# Control_Board.net
KiCad netlist of a schematic drawn in EAGLE
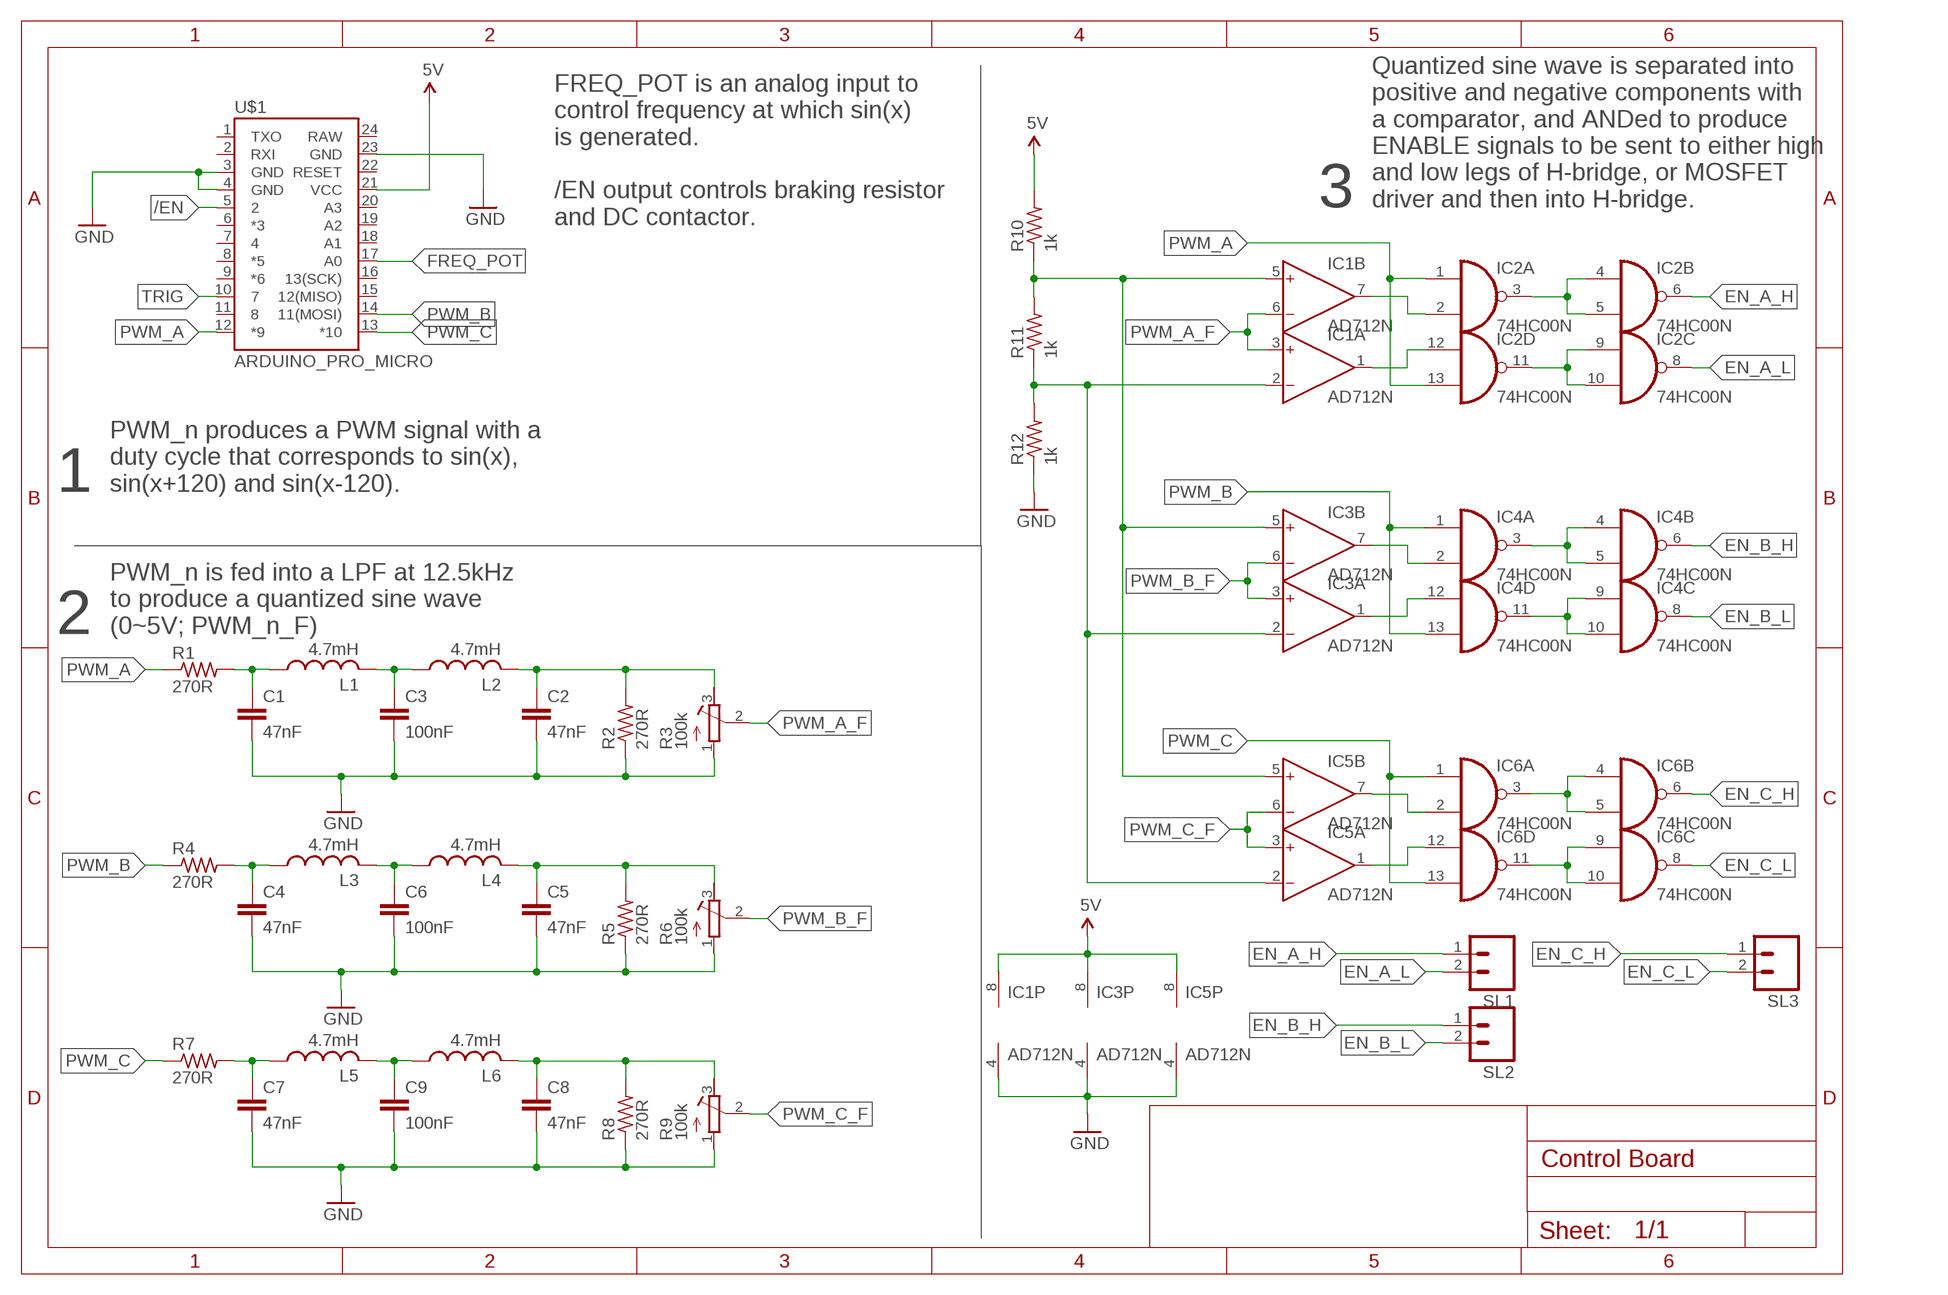
[diagram p0: schematic, sheet 1]

(export (version "E")
  (design (tool "Eeschema 10.0.6"))
  (components
    (comp (ref "C1")
      (value "47nF")
      (footprint "eagle-import:C025-025X050")
      (libsource (lib "eagle-import") (part "C-EU025-025X050"))
    )
    (comp (ref "C2")
      (value "47nF")
      (footprint "eagle-import:C025-025X050")
      (libsource (lib "eagle-import") (part "C-EU025-025X050"))
    )
    (comp (ref "C3")
      (value "100nF")
      (footprint "eagle-import:C025-025X050")
      (libsource (lib "eagle-import") (part "C-EU025-025X050"))
    )
    (comp (ref "C4")
      (value "47nF")
      (footprint "eagle-import:C025-025X050")
      (libsource (lib "eagle-import") (part "C-EU025-025X050"))
    )
    (comp (ref "C5")
      (value "47nF")
      (footprint "eagle-import:C025-025X050")
      (libsource (lib "eagle-import") (part "C-EU025-025X050"))
    )
    (comp (ref "C6")
      (value "100nF")
      (footprint "eagle-import:C025-025X050")
      (libsource (lib "eagle-import") (part "C-EU025-025X050"))
    )
    (comp (ref "C7")
      (value "47nF")
      (footprint "eagle-import:C025-025X050")
      (libsource (lib "eagle-import") (part "C-EU025-025X050"))
    )
    (comp (ref "C8")
      (value "47nF")
      (footprint "eagle-import:C025-025X050")
      (libsource (lib "eagle-import") (part "C-EU025-025X050"))
    )
    (comp (ref "C9")
      (value "100nF")
      (footprint "eagle-import:C025-025X050")
      (libsource (lib "eagle-import") (part "C-EU025-025X050"))
    )
    (comp (ref "IC1")
      (value "AD712N")
      (footprint "eagle-import:DIL08")
      (fields (field (name "MF") "ALTERA CORPORATION") (field (name "MPN") "AD712JNZ"))
      (libsource (lib "eagle-import") (part "AD712N"))
    )
    (comp (ref "IC2")
      (value "74HC00N")
      (footprint "eagle-import:DIL14")
      (libsource (lib "eagle-import") (part "7400NHC"))
    )
    (comp (ref "IC3")
      (value "AD712N")
      (footprint "eagle-import:DIL08")
      (fields (field (name "MF") "ALTERA CORPORATION") (field (name "MPN") "AD712JNZ"))
      (libsource (lib "eagle-import") (part "AD712N"))
    )
    (comp (ref "IC4")
      (value "74HC00N")
      (footprint "eagle-import:DIL14")
      (libsource (lib "eagle-import") (part "7400NHC"))
    )
    (comp (ref "IC5")
      (value "AD712N")
      (footprint "eagle-import:DIL08")
      (fields (field (name "MF") "ALTERA CORPORATION") (field (name "MPN") "AD712JNZ"))
      (libsource (lib "eagle-import") (part "AD712N"))
    )
    (comp (ref "IC6")
      (value "74HC00N")
      (footprint "eagle-import:DIL14")
      (libsource (lib "eagle-import") (part "7400NHC"))
    )
    (comp (ref "L1")
      (value "4.7mH")
      (footprint "eagle-import:0207_12")
      (libsource (lib "eagle-import") (part "L-US0207/12"))
    )
    (comp (ref "L2")
      (value "4.7mH")
      (footprint "eagle-import:0207_12")
      (libsource (lib "eagle-import") (part "L-US0207/12"))
    )
    (comp (ref "L3")
      (value "4.7mH")
      (footprint "eagle-import:0207_12")
      (libsource (lib "eagle-import") (part "L-US0207/12"))
    )
    (comp (ref "L4")
      (value "4.7mH")
      (footprint "eagle-import:0207_12")
      (libsource (lib "eagle-import") (part "L-US0207/12"))
    )
    (comp (ref "L5")
      (value "4.7mH")
      (footprint "eagle-import:0207_12")
      (libsource (lib "eagle-import") (part "L-US0207/12"))
    )
    (comp (ref "L6")
      (value "4.7mH")
      (footprint "eagle-import:0207_12")
      (libsource (lib "eagle-import") (part "L-US0207/12"))
    )
    (comp (ref "R1")
      (value "270R")
      (footprint "eagle-import:0207_7")
      (libsource (lib "eagle-import") (part "R-US_0207/7"))
    )
    (comp (ref "R2")
      (value "270R")
      (footprint "eagle-import:0207_7")
      (libsource (lib "eagle-import") (part "R-US_0207/7"))
    )
    (comp (ref "R3")
      (value "100k")
      (footprint "eagle-import:RTRIM3296W")
      (libsource (lib "eagle-import") (part "R-TRIMM3296W"))
    )
    (comp (ref "R4")
      (value "270R")
      (footprint "eagle-import:0207_7")
      (libsource (lib "eagle-import") (part "R-US_0207/7"))
    )
    (comp (ref "R5")
      (value "270R")
      (footprint "eagle-import:0207_7")
      (libsource (lib "eagle-import") (part "R-US_0207/7"))
    )
    (comp (ref "R6")
      (value "100k")
      (footprint "eagle-import:RTRIM3296W")
      (libsource (lib "eagle-import") (part "R-TRIMM3296W"))
    )
    (comp (ref "R7")
      (value "270R")
      (footprint "eagle-import:0207_7")
      (libsource (lib "eagle-import") (part "R-US_0207/7"))
    )
    (comp (ref "R8")
      (value "270R")
      (footprint "eagle-import:0207_7")
      (libsource (lib "eagle-import") (part "R-US_0207/7"))
    )
    (comp (ref "R9")
      (value "100k")
      (footprint "eagle-import:RTRIM3296W")
      (libsource (lib "eagle-import") (part "R-TRIMM3296W"))
    )
    (comp (ref "R10")
      (value "1k")
      (footprint "eagle-import:0207_7")
      (libsource (lib "eagle-import") (part "R-US_0207/7"))
    )
    (comp (ref "R11")
      (value "1k")
      (footprint "eagle-import:0207_7")
      (libsource (lib "eagle-import") (part "R-US_0207/7"))
    )
    (comp (ref "R12")
      (value "1k")
      (footprint "eagle-import:0207_7")
      (libsource (lib "eagle-import") (part "R-US_0207/7"))
    )
    (comp (ref "SL1")
      (value "M02PTH")
      (footprint "eagle-import:1X02")
      (libsource (lib "eagle-import") (part "M02PTH"))
    )
    (comp (ref "SL2")
      (value "M02PTH")
      (footprint "eagle-import:1X02")
      (libsource (lib "eagle-import") (part "M02PTH"))
    )
    (comp (ref "SL3")
      (value "M02PTH")
      (footprint "eagle-import:1X02")
      (libsource (lib "eagle-import") (part "M02PTH"))
    )
    (comp (ref "U$1")
      (value "ARDUINO_PRO_MICRO")
      (footprint "eagle-import:ARDUINO_PRO_MICRO")
      (libsource (lib "eagle-import") (part "ARDUINO_PRO_MICRO"))
    )
  )
  (nets
    (net (code "1") (name "5V") (class "Default")
      (node (ref "IC1") (pin "8") (pinfunction "V+_8") (pintype "power_in"))
      (node (ref "IC3") (pin "8") (pinfunction "V+_8") (pintype "power_in"))
      (node (ref "IC5") (pin "8") (pinfunction "V+_8") (pintype "power_in"))
      (node (ref "R10") (pin "2") (pinfunction "2_2") (pintype "passive"))
      (node (ref "U$1") (pin "21") (pinfunction "VCC_21") (pintype "bidirectional"))
    )
    (net (code "2") (name "EN_A_H") (class "Default")
      (node (ref "IC2") (pin "6") (pinfunction "O_6") (pintype "output"))
      (node (ref "SL1") (pin "1") (pinfunction "1_1") (pintype "passive"))
    )
    (net (code "3") (name "EN_A_L") (class "Default")
      (node (ref "IC2") (pin "8") (pinfunction "O_8") (pintype "output"))
      (node (ref "SL1") (pin "2") (pinfunction "2_2") (pintype "passive"))
    )
    (net (code "4") (name "EN_B_H") (class "Default")
      (node (ref "IC4") (pin "6") (pinfunction "O_6") (pintype "output"))
      (node (ref "SL2") (pin "1") (pinfunction "1_1") (pintype "passive"))
    )
    (net (code "5") (name "EN_B_L") (class "Default")
      (node (ref "IC4") (pin "8") (pinfunction "O_8") (pintype "output"))
      (node (ref "SL2") (pin "2") (pinfunction "2_2") (pintype "passive"))
    )
    (net (code "6") (name "EN_C_H") (class "Default")
      (node (ref "IC6") (pin "6") (pinfunction "O_6") (pintype "output"))
      (node (ref "SL3") (pin "1") (pinfunction "1_1") (pintype "passive"))
    )
    (net (code "7") (name "EN_C_L") (class "Default")
      (node (ref "IC6") (pin "8") (pinfunction "O_8") (pintype "output"))
      (node (ref "SL3") (pin "2") (pinfunction "2_2") (pintype "passive"))
    )
    (net (code "8") (name "FREQ_POT") (class "Default")
      (node (ref "U$1") (pin "17") (pinfunction "A0_17") (pintype "bidirectional"))
    )
    (net (code "9") (name "GND") (class "Default")
      (node (ref "C1") (pin "2") (pinfunction "2_2") (pintype "passive"))
      (node (ref "C2") (pin "2") (pinfunction "2_2") (pintype "passive"))
      (node (ref "C3") (pin "2") (pinfunction "2_2") (pintype "passive"))
      (node (ref "C4") (pin "2") (pinfunction "2_2") (pintype "passive"))
      (node (ref "C5") (pin "2") (pinfunction "2_2") (pintype "passive"))
      (node (ref "C6") (pin "2") (pinfunction "2_2") (pintype "passive"))
      (node (ref "C7") (pin "2") (pinfunction "2_2") (pintype "passive"))
      (node (ref "C8") (pin "2") (pinfunction "2_2") (pintype "passive"))
      (node (ref "C9") (pin "2") (pinfunction "2_2") (pintype "passive"))
      (node (ref "IC1") (pin "4") (pinfunction "V-_4") (pintype "power_in"))
      (node (ref "IC3") (pin "4") (pinfunction "V-_4") (pintype "power_in"))
      (node (ref "IC5") (pin "4") (pinfunction "V-_4") (pintype "power_in"))
      (node (ref "R12") (pin "1") (pinfunction "1_1") (pintype "passive"))
      (node (ref "R2") (pin "1") (pinfunction "1_1") (pintype "passive"))
      (node (ref "R3") (pin "1") (pinfunction "A_1") (pintype "passive"))
      (node (ref "R5") (pin "1") (pinfunction "1_1") (pintype "passive"))
      (node (ref "R6") (pin "1") (pinfunction "A_1") (pintype "passive"))
      (node (ref "R8") (pin "1") (pinfunction "1_1") (pintype "passive"))
      (node (ref "R9") (pin "1") (pinfunction "A_1") (pintype "passive"))
      (node (ref "U$1") (pin "23") (pinfunction "GND_23") (pintype "bidirectional"))
      (node (ref "U$1") (pin "3") (pinfunction "GND_3") (pintype "bidirectional"))
      (node (ref "U$1") (pin "4") (pinfunction "GND_4") (pintype "bidirectional"))
    )
    (net (code "10") (name "Net-(C1-Pad1)") (class "Default")
      (node (ref "C1") (pin "1") (pinfunction "1_1") (pintype "passive"))
      (node (ref "L1") (pin "1") (pinfunction "1_1") (pintype "passive"))
      (node (ref "R1") (pin "2") (pinfunction "2_2") (pintype "passive"))
    )
    (net (code "11") (name "Net-(C3-Pad1)") (class "Default")
      (node (ref "C3") (pin "1") (pinfunction "1_1") (pintype "passive"))
      (node (ref "L1") (pin "2") (pinfunction "2_2") (pintype "passive"))
      (node (ref "L2") (pin "1") (pinfunction "1_1") (pintype "passive"))
    )
    (net (code "12") (name "Net-(C4-Pad1)") (class "Default")
      (node (ref "C4") (pin "1") (pinfunction "1_1") (pintype "passive"))
      (node (ref "L3") (pin "1") (pinfunction "1_1") (pintype "passive"))
      (node (ref "R4") (pin "2") (pinfunction "2_2") (pintype "passive"))
    )
    (net (code "13") (name "Net-(C6-Pad1)") (class "Default")
      (node (ref "C6") (pin "1") (pinfunction "1_1") (pintype "passive"))
      (node (ref "L3") (pin "2") (pinfunction "2_2") (pintype "passive"))
      (node (ref "L4") (pin "1") (pinfunction "1_1") (pintype "passive"))
    )
    (net (code "14") (name "Net-(C7-Pad1)") (class "Default")
      (node (ref "C7") (pin "1") (pinfunction "1_1") (pintype "passive"))
      (node (ref "L5") (pin "1") (pinfunction "1_1") (pintype "passive"))
      (node (ref "R7") (pin "2") (pinfunction "2_2") (pintype "passive"))
    )
    (net (code "15") (name "Net-(C9-Pad1)") (class "Default")
      (node (ref "C9") (pin "1") (pinfunction "1_1") (pintype "passive"))
      (node (ref "L5") (pin "2") (pinfunction "2_2") (pintype "passive"))
      (node (ref "L6") (pin "1") (pinfunction "1_1") (pintype "passive"))
    )
    (net (code "16") (name "Net-(IC1A-IN-)") (class "Default")
      (node (ref "IC1") (pin "2") (pinfunction "IN-_2") (pintype "input"))
      (node (ref "IC3") (pin "2") (pinfunction "IN-_2") (pintype "input"))
      (node (ref "IC5") (pin "2") (pinfunction "IN-_2") (pintype "input"))
      (node (ref "R11") (pin "1") (pinfunction "1_1") (pintype "passive"))
      (node (ref "R12") (pin "2") (pinfunction "2_2") (pintype "passive"))
    )
    (net (code "17") (name "Net-(IC1A-OUT)") (class "Default")
      (node (ref "IC1") (pin "1") (pinfunction "OUT_1") (pintype "output"))
      (node (ref "IC2") (pin "12") (pinfunction "I0_12") (pintype "input"))
    )
    (net (code "18") (name "Net-(IC1B-IN+)") (class "Default")
      (node (ref "IC1") (pin "5") (pinfunction "IN+_5") (pintype "input"))
      (node (ref "IC3") (pin "5") (pinfunction "IN+_5") (pintype "input"))
      (node (ref "IC5") (pin "5") (pinfunction "IN+_5") (pintype "input"))
      (node (ref "R10") (pin "1") (pinfunction "1_1") (pintype "passive"))
      (node (ref "R11") (pin "2") (pinfunction "2_2") (pintype "passive"))
    )
    (net (code "19") (name "Net-(IC1B-OUT)") (class "Default")
      (node (ref "IC1") (pin "7") (pinfunction "OUT_7") (pintype "output"))
      (node (ref "IC2") (pin "2") (pinfunction "I1_2") (pintype "input"))
    )
    (net (code "20") (name "Net-(IC2A-O)") (class "Default")
      (node (ref "IC2") (pin "3") (pinfunction "O_3") (pintype "output"))
      (node (ref "IC2") (pin "4") (pinfunction "I0_4") (pintype "input"))
      (node (ref "IC2") (pin "5") (pinfunction "I1_5") (pintype "input"))
    )
    (net (code "21") (name "Net-(IC2C-I0)") (class "Default")
      (node (ref "IC2") (pin "10") (pinfunction "I1_10") (pintype "input"))
      (node (ref "IC2") (pin "11") (pinfunction "O_11") (pintype "output"))
      (node (ref "IC2") (pin "9") (pinfunction "I0_9") (pintype "input"))
    )
    (net (code "22") (name "Net-(IC3A-OUT)") (class "Default")
      (node (ref "IC3") (pin "1") (pinfunction "OUT_1") (pintype "output"))
      (node (ref "IC4") (pin "12") (pinfunction "I0_12") (pintype "input"))
    )
    (net (code "23") (name "Net-(IC3B-OUT)") (class "Default")
      (node (ref "IC3") (pin "7") (pinfunction "OUT_7") (pintype "output"))
      (node (ref "IC4") (pin "2") (pinfunction "I1_2") (pintype "input"))
    )
    (net (code "24") (name "Net-(IC4A-O)") (class "Default")
      (node (ref "IC4") (pin "3") (pinfunction "O_3") (pintype "output"))
      (node (ref "IC4") (pin "4") (pinfunction "I0_4") (pintype "input"))
      (node (ref "IC4") (pin "5") (pinfunction "I1_5") (pintype "input"))
    )
    (net (code "25") (name "Net-(IC4C-I0)") (class "Default")
      (node (ref "IC4") (pin "10") (pinfunction "I1_10") (pintype "input"))
      (node (ref "IC4") (pin "11") (pinfunction "O_11") (pintype "output"))
      (node (ref "IC4") (pin "9") (pinfunction "I0_9") (pintype "input"))
    )
    (net (code "26") (name "Net-(IC5A-OUT)") (class "Default")
      (node (ref "IC5") (pin "1") (pinfunction "OUT_1") (pintype "output"))
      (node (ref "IC6") (pin "12") (pinfunction "I0_12") (pintype "input"))
    )
    (net (code "27") (name "Net-(IC5B-OUT)") (class "Default")
      (node (ref "IC5") (pin "7") (pinfunction "OUT_7") (pintype "output"))
      (node (ref "IC6") (pin "2") (pinfunction "I1_2") (pintype "input"))
    )
    (net (code "28") (name "Net-(IC6A-O)") (class "Default")
      (node (ref "IC6") (pin "3") (pinfunction "O_3") (pintype "output"))
      (node (ref "IC6") (pin "4") (pinfunction "I0_4") (pintype "input"))
      (node (ref "IC6") (pin "5") (pinfunction "I1_5") (pintype "input"))
    )
    (net (code "29") (name "Net-(IC6C-I0)") (class "Default")
      (node (ref "IC6") (pin "10") (pinfunction "I1_10") (pintype "input"))
      (node (ref "IC6") (pin "11") (pinfunction "O_11") (pintype "output"))
      (node (ref "IC6") (pin "9") (pinfunction "I0_9") (pintype "input"))
    )
    (net (code "30") (name "Net-(R3-E)") (class "Default")
      (node (ref "C2") (pin "1") (pinfunction "1_1") (pintype "passive"))
      (node (ref "L2") (pin "2") (pinfunction "2_2") (pintype "passive"))
      (node (ref "R2") (pin "2") (pinfunction "2_2") (pintype "passive"))
      (node (ref "R3") (pin "3") (pinfunction "E_3") (pintype "passive"))
    )
    (net (code "31") (name "Net-(R6-E)") (class "Default")
      (node (ref "C5") (pin "1") (pinfunction "1_1") (pintype "passive"))
      (node (ref "L4") (pin "2") (pinfunction "2_2") (pintype "passive"))
      (node (ref "R5") (pin "2") (pinfunction "2_2") (pintype "passive"))
      (node (ref "R6") (pin "3") (pinfunction "E_3") (pintype "passive"))
    )
    (net (code "32") (name "Net-(R9-E)") (class "Default")
      (node (ref "C8") (pin "1") (pinfunction "1_1") (pintype "passive"))
      (node (ref "L6") (pin "2") (pinfunction "2_2") (pintype "passive"))
      (node (ref "R8") (pin "2") (pinfunction "2_2") (pintype "passive"))
      (node (ref "R9") (pin "3") (pinfunction "E_3") (pintype "passive"))
    )
    (net (code "33") (name "PWM_A") (class "Default")
      (node (ref "IC2") (pin "1") (pinfunction "I0_1") (pintype "input"))
      (node (ref "IC2") (pin "13") (pinfunction "I1_13") (pintype "input"))
      (node (ref "R1") (pin "1") (pinfunction "1_1") (pintype "passive"))
      (node (ref "U$1") (pin "12") (pinfunction "*9_12") (pintype "bidirectional"))
    )
    (net (code "34") (name "PWM_A_F") (class "Default")
      (node (ref "IC1") (pin "3") (pinfunction "IN+_3") (pintype "input"))
      (node (ref "IC1") (pin "6") (pinfunction "IN-_6") (pintype "input"))
      (node (ref "R3") (pin "2") (pinfunction "S_2") (pintype "passive"))
    )
    (net (code "35") (name "PWM_B") (class "Default")
      (node (ref "IC4") (pin "1") (pinfunction "I0_1") (pintype "input"))
      (node (ref "IC4") (pin "13") (pinfunction "I1_13") (pintype "input"))
      (node (ref "R4") (pin "1") (pinfunction "1_1") (pintype "passive"))
      (node (ref "U$1") (pin "14") (pinfunction "11(MOSI)_14") (pintype "bidirectional"))
    )
    (net (code "36") (name "PWM_B_F") (class "Default")
      (node (ref "IC3") (pin "3") (pinfunction "IN+_3") (pintype "input"))
      (node (ref "IC3") (pin "6") (pinfunction "IN-_6") (pintype "input"))
      (node (ref "R6") (pin "2") (pinfunction "S_2") (pintype "passive"))
    )
    (net (code "37") (name "PWM_C") (class "Default")
      (node (ref "IC6") (pin "1") (pinfunction "I0_1") (pintype "input"))
      (node (ref "IC6") (pin "13") (pinfunction "I1_13") (pintype "input"))
      (node (ref "R7") (pin "1") (pinfunction "1_1") (pintype "passive"))
      (node (ref "U$1") (pin "13") (pinfunction "*10_13") (pintype "bidirectional"))
    )
    (net (code "38") (name "PWM_C_F") (class "Default")
      (node (ref "IC5") (pin "3") (pinfunction "IN+_3") (pintype "input"))
      (node (ref "IC5") (pin "6") (pinfunction "IN-_6") (pintype "input"))
      (node (ref "R9") (pin "2") (pinfunction "S_2") (pintype "passive"))
    )
    (net (code "39") (name "TRIG") (class "Default")
      (node (ref "U$1") (pin "10") (pinfunction "7_10") (pintype "bidirectional"))
    )
    (net (code "40") (name "unconnected-(U$1-*3-Pad6)") (class "Default")
      (node (ref "U$1") (pin "6") (pinfunction "*3_6") (pintype "bidirectional"))
    )
    (net (code "41") (name "unconnected-(U$1-*5-Pad8)") (class "Default")
      (node (ref "U$1") (pin "8") (pinfunction "*5_8") (pintype "bidirectional"))
    )
    (net (code "42") (name "unconnected-(U$1-*6-Pad9)") (class "Default")
      (node (ref "U$1") (pin "9") (pinfunction "*6_9") (pintype "bidirectional"))
    )
    (net (code "43") (name "unconnected-(U$1-4-Pad7)") (class "Default")
      (node (ref "U$1") (pin "7") (pinfunction "4_7") (pintype "bidirectional"))
    )
    (net (code "44") (name "unconnected-(U$1-8-Pad11)") (class "Default")
      (node (ref "U$1") (pin "11") (pinfunction "8_11") (pintype "bidirectional"))
    )
    (net (code "45") (name "unconnected-(U$1-12(MISO)-Pad15)") (class "Default")
      (node (ref "U$1") (pin "15") (pinfunction "12(MISO)_15") (pintype "bidirectional"))
    )
    (net (code "46") (name "unconnected-(U$1-13(SCK)-Pad16)") (class "Default")
      (node (ref "U$1") (pin "16") (pinfunction "13(SCK)_16") (pintype "bidirectional"))
    )
    (net (code "47") (name "unconnected-(U$1-A1-Pad18)") (class "Default")
      (node (ref "U$1") (pin "18") (pinfunction "A1_18") (pintype "bidirectional"))
    )
    (net (code "48") (name "unconnected-(U$1-A2-Pad19)") (class "Default")
      (node (ref "U$1") (pin "19") (pinfunction "A2_19") (pintype "bidirectional"))
    )
    (net (code "49") (name "unconnected-(U$1-A3-Pad20)") (class "Default")
      (node (ref "U$1") (pin "20") (pinfunction "A3_20") (pintype "bidirectional"))
    )
    (net (code "50") (name "unconnected-(U$1-RAW-Pad24)") (class "Default")
      (node (ref "U$1") (pin "24") (pinfunction "RAW_24") (pintype "bidirectional"))
    )
    (net (code "51") (name "unconnected-(U$1-RESET-Pad22)") (class "Default")
      (node (ref "U$1") (pin "22") (pinfunction "RESET_22") (pintype "bidirectional"))
    )
    (net (code "52") (name "unconnected-(U$1-RXI-Pad2)") (class "Default")
      (node (ref "U$1") (pin "2") (pinfunction "RXI_2") (pintype "bidirectional"))
    )
    (net (code "53") (name "unconnected-(U$1-TXO-Pad1)") (class "Default")
      (node (ref "U$1") (pin "1") (pinfunction "TXO_1") (pintype "bidirectional"))
    )
    (net (code "54") (name "{slash}EN") (class "Default")
      (node (ref "U$1") (pin "5") (pinfunction "2_5") (pintype "bidirectional"))
    )
  )
)
